# PCB-schematic-v1_2.net
KiCad netlist of a schematic drawn in EAGLE
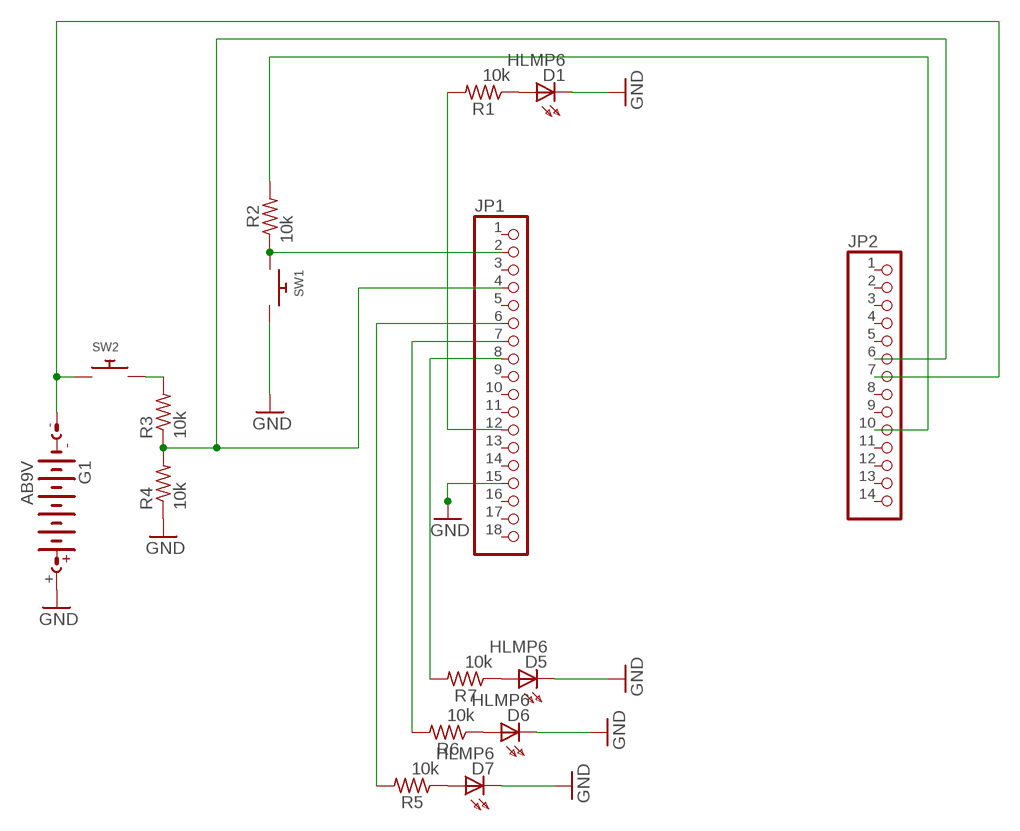
[diagram p0: schematic, sheet 1]

(export (version "E")
  (design (tool "Eeschema 10.0.6"))
  (components
    (comp (ref "D1")
      (value "HLMP6")
      (footprint "eagle-import:HLMP6")
      (fields (field (name "MF") "AGILENT TECHNOLOGIES") (field (name "MPN") "HLMP-6500"))
      (libsource (lib "eagle-import") (part "HLMP6"))
    )
    (comp (ref "D5")
      (value "HLMP6")
      (footprint "eagle-import:HLMP6")
      (fields (field (name "MF") "AGILENT TECHNOLOGIES") (field (name "MPN") "HLMP-6500"))
      (libsource (lib "eagle-import") (part "HLMP6"))
    )
    (comp (ref "D6")
      (value "HLMP6")
      (footprint "eagle-import:HLMP6")
      (fields (field (name "MF") "AGILENT TECHNOLOGIES") (field (name "MPN") "HLMP-6500"))
      (libsource (lib "eagle-import") (part "HLMP6"))
    )
    (comp (ref "D7")
      (value "HLMP6")
      (footprint "eagle-import:HLMP6")
      (fields (field (name "MF") "AGILENT TECHNOLOGIES") (field (name "MPN") "HLMP-6500"))
      (libsource (lib "eagle-import") (part "HLMP6"))
    )
    (comp (ref "G1")
      (value "AB9V")
      (footprint "eagle-import:AB9V")
      (libsource (lib "eagle-import") (part "AB9V"))
    )
    (comp (ref "JP1")
      (value "PINHD-1X18")
      (footprint "eagle-import:1X18")
      (libsource (lib "eagle-import") (part "PINHD-1X18"))
    )
    (comp (ref "JP2")
      (value "PINHD-1X14")
      (footprint "eagle-import:1X14")
      (libsource (lib "eagle-import") (part "PINHD-1X14"))
    )
    (comp (ref "R1")
      (value "10k")
      (footprint "eagle-import:R0805")
      (libsource (lib "eagle-import") (part "R-US_R0805"))
    )
    (comp (ref "R2")
      (value "10k")
      (footprint "eagle-import:R0805")
      (libsource (lib "eagle-import") (part "R-US_R0805"))
    )
    (comp (ref "R3")
      (value "10k")
      (footprint "eagle-import:R0805")
      (libsource (lib "eagle-import") (part "R-US_R0805"))
    )
    (comp (ref "R4")
      (value "10k")
      (footprint "eagle-import:R0805")
      (libsource (lib "eagle-import") (part "R-US_R0805"))
    )
    (comp (ref "R5")
      (value "10k")
      (footprint "eagle-import:R0805")
      (libsource (lib "eagle-import") (part "R-US_R0805"))
    )
    (comp (ref "R6")
      (value "10k")
      (footprint "eagle-import:R0805")
      (libsource (lib "eagle-import") (part "R-US_R0805"))
    )
    (comp (ref "R7")
      (value "10k")
      (footprint "eagle-import:R0805")
      (libsource (lib "eagle-import") (part "R-US_R0805"))
    )
    (comp (ref "SW1")
      (value "SWITCH_PUSHBUTTONSOFTTOUCHSMD_SJ")
      (footprint "eagle-import:PUSHBUTTON_SMD_SJ")
      (libsource (lib "eagle-import") (part "SWITCH_PUSHBUTTONSOFTTOUCHSMD_SJ"))
    )
    (comp (ref "SW2")
      (value "SWITCH_PUSHBUTTONSOFTTOUCHSMD_SJ")
      (footprint "eagle-import:PUSHBUTTON_SMD_SJ")
      (libsource (lib "eagle-import") (part "SWITCH_PUSHBUTTONSOFTTOUCHSMD_SJ"))
    )
  )
  (nets
    (net (code "1") (name "GND") (class "Default")
      (node (ref "D1") (pin "K") (pinfunction "K_K") (pintype "passive"))
      (node (ref "D5") (pin "K") (pinfunction "K_K") (pintype "passive"))
      (node (ref "D6") (pin "K") (pinfunction "K_K") (pintype "passive"))
      (node (ref "D7") (pin "K") (pinfunction "K_K") (pintype "passive"))
      (node (ref "G1") (pin "+") (pinfunction "+_+") (pintype "passive"))
      (node (ref "JP1") (pin "15") (pinfunction "15_15") (pintype "passive"))
      (node (ref "R4") (pin "1") (pinfunction "1_1") (pintype "passive"))
      (node (ref "SW1") (pin "P$2") (pinfunction "P$2_P$2") (pintype "passive"))
    )
    (net (code "2") (name "Net-(D1-PadA)") (class "Default")
      (node (ref "D1") (pin "A") (pinfunction "A_A") (pintype "passive"))
      (node (ref "R1") (pin "1") (pinfunction "1_1") (pintype "passive"))
    )
    (net (code "3") (name "Net-(D5-PadA)") (class "Default")
      (node (ref "D5") (pin "A") (pinfunction "A_A") (pintype "passive"))
      (node (ref "R7") (pin "1") (pinfunction "1_1") (pintype "passive"))
    )
    (net (code "4") (name "Net-(D6-PadA)") (class "Default")
      (node (ref "D6") (pin "A") (pinfunction "A_A") (pintype "passive"))
      (node (ref "R6") (pin "1") (pinfunction "1_1") (pintype "passive"))
    )
    (net (code "5") (name "Net-(D7-PadA)") (class "Default")
      (node (ref "D7") (pin "A") (pinfunction "A_A") (pintype "passive"))
      (node (ref "R5") (pin "1") (pinfunction "1_1") (pintype "passive"))
    )
    (net (code "6") (name "Net-(G1-Pad-)") (class "Default")
      (node (ref "G1") (pin "-") (pinfunction "-_-") (pintype "passive"))
      (node (ref "JP2") (pin "7") (pinfunction "7_7") (pintype "passive"))
      (node (ref "SW2") (pin "P$1") (pinfunction "P$1_P$1") (pintype "passive"))
    )
    (net (code "7") (name "Net-(JP1-Pad2)") (class "Default")
      (node (ref "JP1") (pin "2") (pinfunction "2_2") (pintype "passive"))
      (node (ref "R2") (pin "1") (pinfunction "1_1") (pintype "passive"))
      (node (ref "SW1") (pin "P$1") (pinfunction "P$1_P$1") (pintype "passive"))
    )
    (net (code "8") (name "Net-(JP1-Pad4)") (class "Default")
      (node (ref "JP1") (pin "4") (pinfunction "4_4") (pintype "passive"))
      (node (ref "JP2") (pin "6") (pinfunction "6_6") (pintype "passive"))
      (node (ref "R3") (pin "1") (pinfunction "1_1") (pintype "passive"))
      (node (ref "R4") (pin "2") (pinfunction "2_2") (pintype "passive"))
    )
    (net (code "9") (name "Net-(JP1-Pad6)") (class "Default")
      (node (ref "JP1") (pin "6") (pinfunction "6_6") (pintype "passive"))
      (node (ref "R5") (pin "2") (pinfunction "2_2") (pintype "passive"))
    )
    (net (code "10") (name "Net-(JP1-Pad7)") (class "Default")
      (node (ref "JP1") (pin "7") (pinfunction "7_7") (pintype "passive"))
      (node (ref "R6") (pin "2") (pinfunction "2_2") (pintype "passive"))
    )
    (net (code "11") (name "Net-(JP1-Pad8)") (class "Default")
      (node (ref "JP1") (pin "8") (pinfunction "8_8") (pintype "passive"))
      (node (ref "R7") (pin "2") (pinfunction "2_2") (pintype "passive"))
    )
    (net (code "12") (name "Net-(JP1-Pad12)") (class "Default")
      (node (ref "JP1") (pin "12") (pinfunction "12_12") (pintype "passive"))
      (node (ref "R1") (pin "2") (pinfunction "2_2") (pintype "passive"))
    )
    (net (code "13") (name "Net-(JP2-Pad10)") (class "Default")
      (node (ref "JP2") (pin "10") (pinfunction "10_10") (pintype "passive"))
      (node (ref "R2") (pin "2") (pinfunction "2_2") (pintype "passive"))
    )
    (net (code "14") (name "Net-(R3-Pad2)") (class "Default")
      (node (ref "R3") (pin "2") (pinfunction "2_2") (pintype "passive"))
      (node (ref "SW2") (pin "P$2") (pinfunction "P$2_P$2") (pintype "passive"))
    )
    (net (code "15") (name "unconnected-(JP1-Pad1)") (class "Default")
      (node (ref "JP1") (pin "1") (pinfunction "1_1") (pintype "passive"))
    )
    (net (code "16") (name "unconnected-(JP1-Pad3)") (class "Default")
      (node (ref "JP1") (pin "3") (pinfunction "3_3") (pintype "passive"))
    )
    (net (code "17") (name "unconnected-(JP1-Pad5)") (class "Default")
      (node (ref "JP1") (pin "5") (pinfunction "5_5") (pintype "passive"))
    )
    (net (code "18") (name "unconnected-(JP1-Pad9)") (class "Default")
      (node (ref "JP1") (pin "9") (pinfunction "9_9") (pintype "passive"))
    )
    (net (code "19") (name "unconnected-(JP1-Pad10)") (class "Default")
      (node (ref "JP1") (pin "10") (pinfunction "10_10") (pintype "passive"))
    )
    (net (code "20") (name "unconnected-(JP1-Pad11)") (class "Default")
      (node (ref "JP1") (pin "11") (pinfunction "11_11") (pintype "passive"))
    )
    (net (code "21") (name "unconnected-(JP1-Pad13)") (class "Default")
      (node (ref "JP1") (pin "13") (pinfunction "13_13") (pintype "passive"))
    )
    (net (code "22") (name "unconnected-(JP1-Pad14)") (class "Default")
      (node (ref "JP1") (pin "14") (pinfunction "14_14") (pintype "passive"))
    )
    (net (code "23") (name "unconnected-(JP1-Pad16)") (class "Default")
      (node (ref "JP1") (pin "16") (pinfunction "16_16") (pintype "passive"))
    )
    (net (code "24") (name "unconnected-(JP1-Pad17)") (class "Default")
      (node (ref "JP1") (pin "17") (pinfunction "17_17") (pintype "passive"))
    )
    (net (code "25") (name "unconnected-(JP1-Pad18)") (class "Default")
      (node (ref "JP1") (pin "18") (pinfunction "18_18") (pintype "passive"))
    )
    (net (code "26") (name "unconnected-(JP2-Pad1)") (class "Default")
      (node (ref "JP2") (pin "1") (pinfunction "1_1") (pintype "passive"))
    )
    (net (code "27") (name "unconnected-(JP2-Pad2)") (class "Default")
      (node (ref "JP2") (pin "2") (pinfunction "2_2") (pintype "passive"))
    )
    (net (code "28") (name "unconnected-(JP2-Pad3)") (class "Default")
      (node (ref "JP2") (pin "3") (pinfunction "3_3") (pintype "passive"))
    )
    (net (code "29") (name "unconnected-(JP2-Pad4)") (class "Default")
      (node (ref "JP2") (pin "4") (pinfunction "4_4") (pintype "passive"))
    )
    (net (code "30") (name "unconnected-(JP2-Pad5)") (class "Default")
      (node (ref "JP2") (pin "5") (pinfunction "5_5") (pintype "passive"))
    )
    (net (code "31") (name "unconnected-(JP2-Pad8)") (class "Default")
      (node (ref "JP2") (pin "8") (pinfunction "8_8") (pintype "passive"))
    )
    (net (code "32") (name "unconnected-(JP2-Pad9)") (class "Default")
      (node (ref "JP2") (pin "9") (pinfunction "9_9") (pintype "passive"))
    )
    (net (code "33") (name "unconnected-(JP2-Pad11)") (class "Default")
      (node (ref "JP2") (pin "11") (pinfunction "11_11") (pintype "passive"))
    )
    (net (code "34") (name "unconnected-(JP2-Pad12)") (class "Default")
      (node (ref "JP2") (pin "12") (pinfunction "12_12") (pintype "passive"))
    )
    (net (code "35") (name "unconnected-(JP2-Pad13)") (class "Default")
      (node (ref "JP2") (pin "13") (pinfunction "13_13") (pintype "passive"))
    )
    (net (code "36") (name "unconnected-(JP2-Pad14)") (class "Default")
      (node (ref "JP2") (pin "14") (pinfunction "14_14") (pintype "passive"))
    )
  )
)
